# Moteino_Leo-OLM.net
KiCad netlist of a schematic drawn in EAGLE
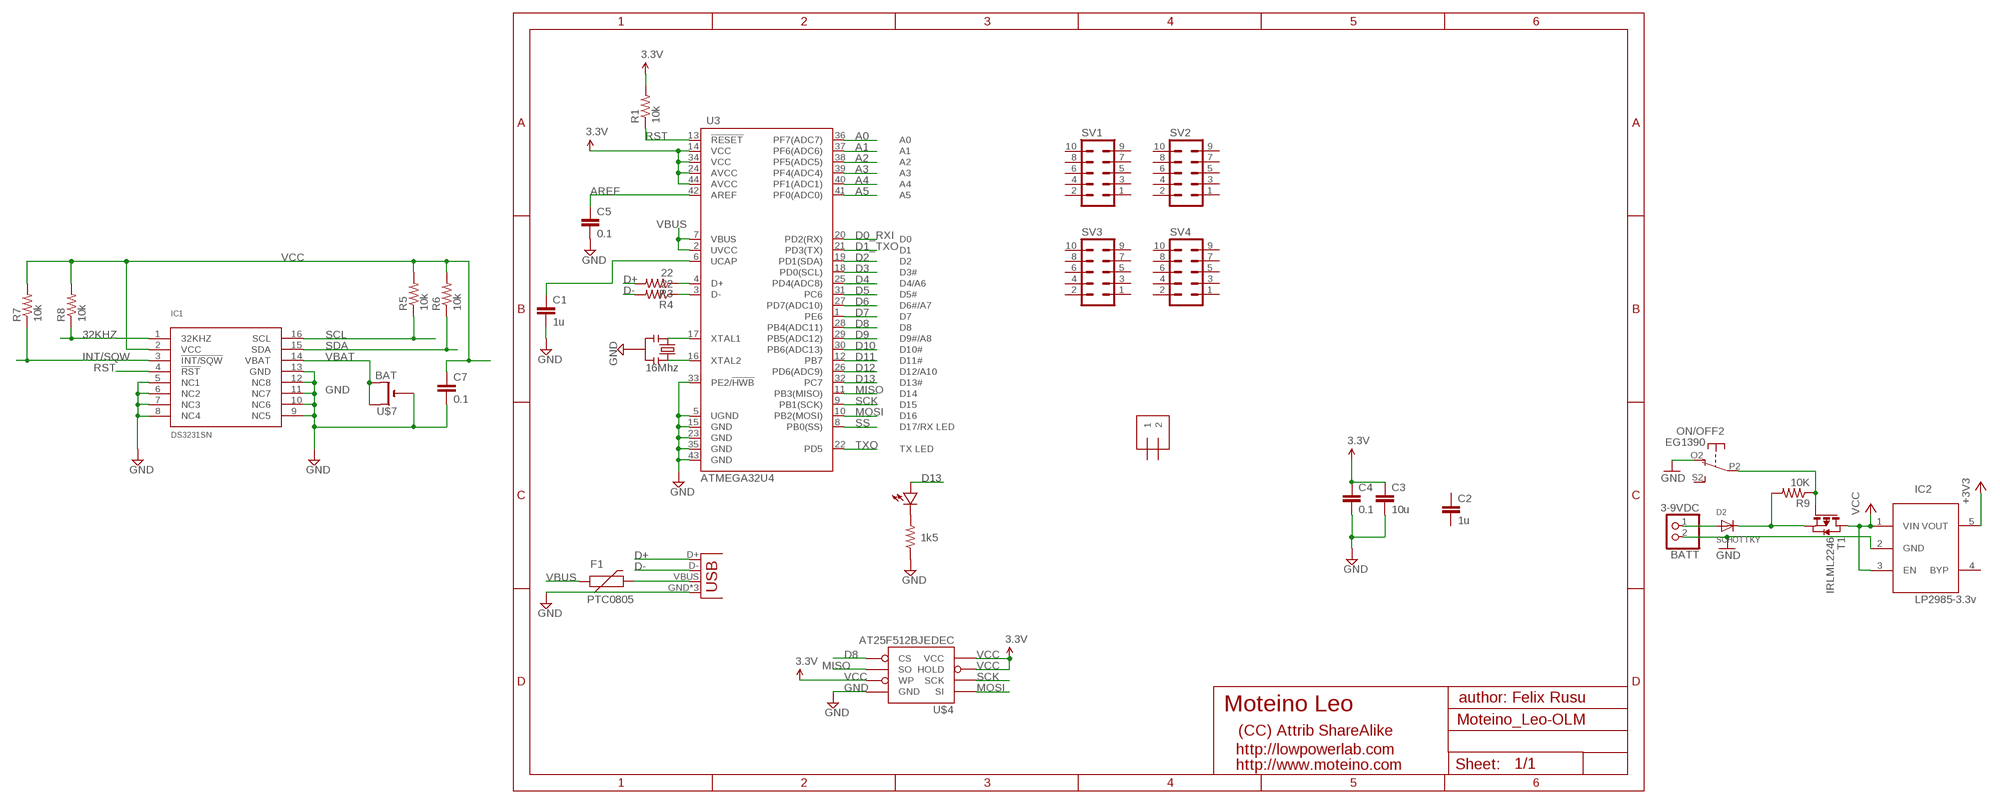
[diagram p0: schematic, sheet 1]

(export (version "E")
  (design (tool "Eeschema 10.0.6"))
  (components
    (comp (ref "BATT")
      (value "3-9VDC")
      (footprint "eagle-import:JST-PH-2-SMT-RA")
      (libsource (lib "eagle-import") (part "JST_2PIN-SMT-RA"))
    )
    (comp (ref "C1")
      (value "1u")
      (footprint "eagle-import:0603-CAP")
      (libsource (lib "eagle-import") (part "CAP0603-CAP"))
    )
    (comp (ref "C2")
      (value "1u")
      (footprint "eagle-import:0603-CAP")
      (libsource (lib "eagle-import") (part "CAP0603-CAP"))
    )
    (comp (ref "C3")
      (value "10u")
      (footprint "eagle-import:0805-CAP")
      (libsource (lib "eagle-import") (part "CAP0805-CAP"))
    )
    (comp (ref "C4")
      (value "0.1")
      (footprint "eagle-import:0603-CAP")
      (libsource (lib "eagle-import") (part "CAP0603-CAP"))
    )
    (comp (ref "C5")
      (value "0.1")
      (footprint "eagle-import:0603-CAP")
      (libsource (lib "eagle-import") (part "CAP0603-CAP"))
    )
    (comp (ref "C7")
      (value "0.1")
      (footprint "eagle-import:0603-CAP")
      (libsource (lib "eagle-import") (part "CAP0603-CAP"))
    )
    (comp (ref "D2")
      (value "SCHOTTKY")
      (footprint "eagle-import:SOD-123")
      (libsource (lib "eagle-import") (part "DIODESOD-123"))
    )
    (comp (ref "F1")
      (value "PTC0805")
      (footprint "eagle-import:0805-PTC")
      (libsource (lib "eagle-import") (part "PTC0805"))
    )
    (comp (ref "IC1")
      (value "DS3231SN")
      (footprint "eagle-import:SO16W")
      (libsource (lib "eagle-import") (part "DS3231SN"))
    )
    (comp (ref "IC2")
      (value "LP2985-3.3v")
      (footprint "eagle-import:SOT23-5L")
      (libsource (lib "eagle-import") (part "LP298XS"))
    )
    (comp (ref "J1")
      (value "1X2-3.5MM")
      (footprint "eagle-import:1X2-3.5MM")
      (libsource (lib "eagle-import") (part "1X2-3.5MM"))
    )
    (comp (ref "JP3")
      (value "USB-MICROB")
      (footprint "eagle-import:USB-MICROB")
      (libsource (lib "eagle-import") (part "USB-MICROB"))
    )
    (comp (ref "ON/OFF")
      (value "EG1390")
      (footprint "eagle-import:EG1390")
      (libsource (lib "eagle-import") (part "DPDT-EG1390"))
    )
    (comp (ref "R1")
      (value "10k")
      (footprint "eagle-import:0603-RES")
      (libsource (lib "eagle-import") (part "RESISTOR0603-RES"))
    )
    (comp (ref "R2")
      (value "1k5")
      (footprint "eagle-import:0603-RES")
      (libsource (lib "eagle-import") (part "RESISTOR0603-RES"))
    )
    (comp (ref "R3")
      (value "22")
      (footprint "eagle-import:0603-RES")
      (libsource (lib "eagle-import") (part "RESISTOR0603-RES"))
    )
    (comp (ref "R4")
      (value "22")
      (footprint "eagle-import:0603-RES")
      (libsource (lib "eagle-import") (part "RESISTOR0603-RES"))
    )
    (comp (ref "R5")
      (value "10k")
      (footprint "eagle-import:0603-RES")
      (libsource (lib "eagle-import") (part "RESISTOR0603-RES"))
    )
    (comp (ref "R6")
      (value "10k")
      (footprint "eagle-import:0603-RES")
      (libsource (lib "eagle-import") (part "RESISTOR0603-RES"))
    )
    (comp (ref "R7")
      (value "10k")
      (footprint "eagle-import:0603-RES")
      (libsource (lib "eagle-import") (part "RESISTOR0603-RES"))
    )
    (comp (ref "R8")
      (value "10k")
      (footprint "eagle-import:0603-RES")
      (libsource (lib "eagle-import") (part "RESISTOR0603-RES"))
    )
    (comp (ref "R9")
      (value "10K")
      (footprint "eagle-import:R0805")
      (libsource (lib "eagle-import") (part "R-US_R0805"))
    )
    (comp (ref "SV1")
      (value "MA05-2")
      (footprint "eagle-import:MA05-2")
      (libsource (lib "eagle-import") (part "MA05-2"))
    )
    (comp (ref "SV2")
      (value "MA05-2")
      (footprint "eagle-import:MA05-2")
      (libsource (lib "eagle-import") (part "MA05-2"))
    )
    (comp (ref "SV3")
      (value "MA05-2")
      (footprint "eagle-import:MA05-2")
      (libsource (lib "eagle-import") (part "MA05-2"))
    )
    (comp (ref "SV4")
      (value "MA05-2")
      (footprint "eagle-import:MA05-2")
      (libsource (lib "eagle-import") (part "MA05-2"))
    )
    (comp (ref "T1")
      (value "IRLML2246")
      (footprint "eagle-import:SOT-23")
      (libsource (lib "eagle-import") (part "PMOSSOT23"))
    )
    (comp (ref "U$2")
      (value "LED0603")
      (footprint "eagle-import:0603-LED")
      (libsource (lib "eagle-import") (part "LED0603"))
    )
    (comp (ref "U$4")
      (value "AT25F512BJEDEC")
      (footprint "eagle-import:SO08")
      (libsource (lib "eagle-import") (part "AT25F512BJEDEC"))
    )
    (comp (ref "U$7")
      (value "BAT")
      (footprint "eagle-import:CR1220-SMD")
      (libsource (lib "eagle-import") (part "CR1220SMT"))
    )
    (comp (ref "U3")
      (value "ATMEGA32U4")
      (footprint "eagle-import:QFN-44-NOPAD")
      (libsource (lib "eagle-import") (part "ATMEGA32U4QFN2"))
    )
    (comp (ref "X1")
      (value "16Mhz")
      (footprint "eagle-import:RESONATOR-SMD")
      (libsource (lib "eagle-import") (part "RESONATORSMD"))
    )
  )
  (nets
    (net (code "1") (name "+3V3") (class "Default")
      (node (ref "IC2") (pin "5") (pinfunction "VOUT_5") (pintype "bidirectional"))
    )
    (net (code "2") (name "/32KHZ") (class "Default")
      (node (ref "IC1") (pin "1") (pinfunction "32KHZ_1") (pintype "bidirectional"))
      (node (ref "R8") (pin "1") (pinfunction "1_1") (pintype "passive"))
    )
    (net (code "3") (name "/A0") (class "Default")
      (node (ref "U3") (pin "36") (pinfunction "PF7(ADC7)_36") (pintype "bidirectional"))
    )
    (net (code "4") (name "/A1") (class "Default")
      (node (ref "U3") (pin "37") (pinfunction "PF6(ADC6)_37") (pintype "bidirectional"))
    )
    (net (code "5") (name "/A2") (class "Default")
      (node (ref "U3") (pin "38") (pinfunction "PF5(ADC5)_38") (pintype "bidirectional"))
    )
    (net (code "6") (name "/A3") (class "Default")
      (node (ref "U3") (pin "39") (pinfunction "PF4(ADC4)_39") (pintype "bidirectional"))
    )
    (net (code "7") (name "/A4") (class "Default")
      (node (ref "U3") (pin "40") (pinfunction "PF1(ADC1)_40") (pintype "bidirectional"))
    )
    (net (code "8") (name "/A5") (class "Default")
      (node (ref "U3") (pin "41") (pinfunction "PF0(ADC0)_41") (pintype "bidirectional"))
    )
    (net (code "9") (name "/AREF") (class "Default")
      (node (ref "C5") (pin "1") (pinfunction "1_1") (pintype "passive"))
      (node (ref "U3") (pin "42") (pinfunction "AREF_42") (pintype "bidirectional"))
    )
    (net (code "10") (name "/D+") (class "Default")
      (node (ref "JP3") (pin "D+") (pinfunction "D+_D+") (pintype "bidirectional"))
      (node (ref "R3") (pin "2") (pinfunction "2_2") (pintype "passive"))
    )
    (net (code "11") (name "/D-") (class "Default")
      (node (ref "JP3") (pin "D-") (pinfunction "D-_D-") (pintype "bidirectional"))
      (node (ref "R4") (pin "2") (pinfunction "2_2") (pintype "passive"))
    )
    (net (code "12") (name "/D0_RXI") (class "Default")
      (node (ref "U3") (pin "20") (pinfunction "PD2(RX)_20") (pintype "bidirectional"))
    )
    (net (code "13") (name "/D1_TXO") (class "Default")
      (node (ref "U3") (pin "21") (pinfunction "PD3(TX)_21") (pintype "bidirectional"))
    )
    (net (code "14") (name "/D2") (class "Default")
      (node (ref "U3") (pin "19") (pinfunction "PD1(SDA)_19") (pintype "bidirectional"))
    )
    (net (code "15") (name "/D3") (class "Default")
      (node (ref "U3") (pin "18") (pinfunction "PD0(SCL)_18") (pintype "bidirectional"))
    )
    (net (code "16") (name "/D4") (class "Default")
      (node (ref "U3") (pin "25") (pinfunction "PD4(ADC8)_25") (pintype "bidirectional"))
    )
    (net (code "17") (name "/D5") (class "Default")
      (node (ref "U3") (pin "31") (pinfunction "PC6_31") (pintype "bidirectional"))
    )
    (net (code "18") (name "/D6") (class "Default")
      (node (ref "U3") (pin "27") (pinfunction "PD7(ADC10)_27") (pintype "bidirectional"))
    )
    (net (code "19") (name "/D7") (class "Default")
      (node (ref "U3") (pin "1") (pinfunction "PE6_1") (pintype "bidirectional"))
    )
    (net (code "20") (name "/D8") (class "Default")
      (node (ref "U$4") (pin "1_CS") (pinfunction "CS_1_CS") (pintype "bidirectional"))
      (node (ref "U3") (pin "28") (pinfunction "PB4(ADC11)_28") (pintype "bidirectional"))
    )
    (net (code "21") (name "/D9") (class "Default")
      (node (ref "U3") (pin "29") (pinfunction "PB5(ADC12)_29") (pintype "bidirectional"))
    )
    (net (code "22") (name "/D10") (class "Default")
      (node (ref "U3") (pin "30") (pinfunction "PB6(ADC13)_30") (pintype "bidirectional"))
    )
    (net (code "23") (name "/D11") (class "Default")
      (node (ref "U3") (pin "12") (pinfunction "PB7_12") (pintype "bidirectional"))
    )
    (net (code "24") (name "/D12") (class "Default")
      (node (ref "U3") (pin "26") (pinfunction "PD6(ADC9)_26") (pintype "bidirectional"))
    )
    (net (code "25") (name "/D13") (class "Default")
      (node (ref "U$2") (pin "PLUS") (pinfunction "PLUS_PLUS") (pintype "passive"))
      (node (ref "U3") (pin "32") (pinfunction "PC7_32") (pintype "bidirectional"))
    )
    (net (code "26") (name "/INT{slash}SQW") (class "Default")
      (node (ref "IC1") (pin "3") (pinfunction "~{INT/SQW}_3") (pintype "bidirectional"))
      (node (ref "R7") (pin "1") (pinfunction "1_1") (pintype "passive"))
    )
    (net (code "27") (name "/MISO") (class "Default")
      (node (ref "U$4") (pin "2_SO") (pinfunction "SO_2_SO") (pintype "bidirectional"))
      (node (ref "U3") (pin "11") (pinfunction "PB3(MISO)_11") (pintype "bidirectional"))
    )
    (net (code "28") (name "/MOSI") (class "Default")
      (node (ref "U$4") (pin "5_SI") (pinfunction "SI_5_SI") (pintype "bidirectional"))
      (node (ref "U3") (pin "10") (pinfunction "PB2(MOSI)_10") (pintype "bidirectional"))
    )
    (net (code "29") (name "/RST") (class "Default")
      (node (ref "IC1") (pin "4") (pinfunction "~{RST}_4") (pintype "bidirectional"))
      (node (ref "R1") (pin "1") (pinfunction "1_1") (pintype "passive"))
      (node (ref "U3") (pin "13") (pinfunction "~{RESET}_13") (pintype "bidirectional"))
    )
    (net (code "30") (name "/SCK") (class "Default")
      (node (ref "U$4") (pin "6_SCK") (pinfunction "SCK_6_SCK") (pintype "bidirectional"))
      (node (ref "U3") (pin "9") (pinfunction "PB1(SCK)_9") (pintype "bidirectional"))
    )
    (net (code "31") (name "/SCL") (class "Default")
      (node (ref "IC1") (pin "16") (pinfunction "SCL_16") (pintype "bidirectional"))
      (node (ref "R5") (pin "1") (pinfunction "1_1") (pintype "passive"))
    )
    (net (code "32") (name "/SDA") (class "Default")
      (node (ref "IC1") (pin "15") (pinfunction "SDA_15") (pintype "bidirectional"))
      (node (ref "R6") (pin "1") (pinfunction "1_1") (pintype "passive"))
    )
    (net (code "33") (name "/SS") (class "Default")
      (node (ref "U3") (pin "8") (pinfunction "PB0(SS)_8") (pintype "bidirectional"))
    )
    (net (code "34") (name "/TXO") (class "Default")
      (node (ref "U3") (pin "22") (pinfunction "PD5_22") (pintype "bidirectional"))
    )
    (net (code "35") (name "/VBAT") (class "Default")
      (node (ref "IC1") (pin "14") (pinfunction "VBAT_14") (pintype "bidirectional"))
      (node (ref "U$7") (pin "+$1") (pinfunction "+_+$1") (pintype "passive"))
      (node (ref "U$7") (pin "+$2") (pinfunction "+1_+$2") (pintype "passive"))
    )
    (net (code "36") (name "/VBUS") (class "Default")
      (node (ref "F1") (pin "1") (pinfunction "1_1") (pintype "bidirectional"))
      (node (ref "U3") (pin "2") (pinfunction "UVCC_2") (pintype "bidirectional"))
      (node (ref "U3") (pin "7") (pinfunction "VBUS_7") (pintype "bidirectional"))
    )
    (net (code "37") (name "3.3V") (class "Default")
      (node (ref "C3") (pin "1") (pinfunction "1_1") (pintype "passive"))
      (node (ref "C4") (pin "1") (pinfunction "1_1") (pintype "passive"))
      (node (ref "C7") (pin "1") (pinfunction "1_1") (pintype "passive"))
      (node (ref "IC1") (pin "2") (pinfunction "VCC_2") (pintype "bidirectional"))
      (node (ref "IC2") (pin "1") (pinfunction "VIN_1") (pintype "bidirectional"))
      (node (ref "IC2") (pin "3") (pinfunction "EN_3") (pintype "bidirectional"))
      (node (ref "R1") (pin "2") (pinfunction "2_2") (pintype "passive"))
      (node (ref "R5") (pin "2") (pinfunction "2_2") (pintype "passive"))
      (node (ref "R6") (pin "2") (pinfunction "2_2") (pintype "passive"))
      (node (ref "R7") (pin "2") (pinfunction "2_2") (pintype "passive"))
      (node (ref "R8") (pin "2") (pinfunction "2_2") (pintype "passive"))
      (node (ref "T1") (pin "1") (pinfunction "D_1") (pintype "passive"))
      (node (ref "U$4") (pin "3_WP") (pinfunction "WP_3_WP") (pintype "bidirectional"))
      (node (ref "U$4") (pin "7_HOLD") (pinfunction "HOLD_7_HOLD") (pintype "bidirectional"))
      (node (ref "U$4") (pin "8_VCC") (pinfunction "VCC_8_VCC") (pintype "bidirectional"))
      (node (ref "U3") (pin "14") (pinfunction "VCC_14") (pintype "bidirectional"))
      (node (ref "U3") (pin "24") (pinfunction "AVCC_24") (pintype "bidirectional"))
      (node (ref "U3") (pin "34") (pinfunction "VCC_34") (pintype "bidirectional"))
      (node (ref "U3") (pin "44") (pinfunction "AVCC_44") (pintype "bidirectional"))
    )
    (net (code "38") (name "GND") (class "Default")
      (node (ref "BATT") (pin "2") (pinfunction "1_2") (pintype "passive"))
      (node (ref "C1") (pin "2") (pinfunction "2_2") (pintype "passive"))
      (node (ref "C3") (pin "2") (pinfunction "2_2") (pintype "passive"))
      (node (ref "C4") (pin "2") (pinfunction "2_2") (pintype "passive"))
      (node (ref "C5") (pin "2") (pinfunction "2_2") (pintype "passive"))
      (node (ref "C7") (pin "2") (pinfunction "2_2") (pintype "passive"))
      (node (ref "IC1") (pin "10") (pinfunction "NC6_10") (pintype "bidirectional"))
      (node (ref "IC1") (pin "11") (pinfunction "NC7_11") (pintype "bidirectional"))
      (node (ref "IC1") (pin "12") (pinfunction "NC8_12") (pintype "bidirectional"))
      (node (ref "IC1") (pin "13") (pinfunction "GND_13") (pintype "bidirectional"))
      (node (ref "IC1") (pin "5") (pinfunction "NC1_5") (pintype "bidirectional"))
      (node (ref "IC1") (pin "6") (pinfunction "NC2_6") (pintype "bidirectional"))
      (node (ref "IC1") (pin "7") (pinfunction "NC3_7") (pintype "bidirectional"))
      (node (ref "IC1") (pin "8") (pinfunction "NC4_8") (pintype "bidirectional"))
      (node (ref "IC1") (pin "9") (pinfunction "NC5_9") (pintype "bidirectional"))
      (node (ref "IC2") (pin "2") (pinfunction "GND_2") (pintype "bidirectional"))
      (node (ref "JP3") (pin "GND") (pinfunction "GND_GND") (pintype "bidirectional"))
      (node (ref "JP3") (pin "MT1") (pinfunction "GND_MT1") (pintype "bidirectional"))
      (node (ref "JP3") (pin "MT2") (pinfunction "GND_MT2") (pintype "bidirectional"))
      (node (ref "ON/OFF") (pin "O2") (pinfunction "O_O2") (pintype "passive"))
      (node (ref "R2") (pin "1") (pinfunction "1_1") (pintype "passive"))
      (node (ref "U$4") (pin "4_GND") (pinfunction "GND_4_GND") (pintype "bidirectional"))
      (node (ref "U$7") (pin "-") (pinfunction "-_-") (pintype "passive"))
      (node (ref "U3") (pin "15") (pinfunction "GND_15") (pintype "bidirectional"))
      (node (ref "U3") (pin "23") (pinfunction "GND_23") (pintype "bidirectional"))
      (node (ref "U3") (pin "33") (pinfunction "PE2/~{HWB}_33") (pintype "bidirectional"))
      (node (ref "U3") (pin "35") (pinfunction "GND_35") (pintype "bidirectional"))
      (node (ref "U3") (pin "43") (pinfunction "GND_43") (pintype "bidirectional"))
      (node (ref "U3") (pin "5") (pinfunction "UGND_5") (pintype "bidirectional"))
      (node (ref "X1") (pin "2") (pinfunction "2_2") (pintype "passive"))
    )
    (net (code "39") (name "Net-(BATT-2)") (class "Default")
      (node (ref "BATT") (pin "1") (pinfunction "2_1") (pintype "passive"))
      (node (ref "D2") (pin "A") (pinfunction "A_A") (pintype "passive"))
    )
    (net (code "40") (name "Net-(F1-Pad2)") (class "Default")
      (node (ref "F1") (pin "2") (pinfunction "2_2") (pintype "bidirectional"))
      (node (ref "JP3") (pin "VBUS") (pinfunction "VBUS_VBUS") (pintype "bidirectional"))
    )
    (net (code "41") (name "Net-(ON/OFFB-P)") (class "Default")
      (node (ref "ON/OFF") (pin "P2") (pinfunction "P_P2") (pintype "passive"))
      (node (ref "R9") (pin "1") (pinfunction "1_1") (pintype "passive"))
      (node (ref "T1") (pin "3") (pinfunction "G_3") (pintype "passive"))
    )
    (net (code "42") (name "Net-(R2-Pad2)") (class "Default")
      (node (ref "R2") (pin "2") (pinfunction "2_2") (pintype "passive"))
      (node (ref "U$2") (pin "MINUS") (pinfunction "MINUS_MINUS") (pintype "passive"))
    )
    (net (code "43") (name "Net-(T1-S)") (class "Default")
      (node (ref "D2") (pin "C") (pinfunction "C_C") (pintype "passive"))
      (node (ref "R9") (pin "2") (pinfunction "2_2") (pintype "passive"))
      (node (ref "T1") (pin "2") (pinfunction "S_2") (pintype "passive"))
    )
    (net (code "44") (name "Net-(U3-D+)") (class "Default")
      (node (ref "R3") (pin "1") (pinfunction "1_1") (pintype "passive"))
      (node (ref "U3") (pin "4") (pinfunction "D+_4") (pintype "bidirectional"))
    )
    (net (code "45") (name "Net-(U3-D-)") (class "Default")
      (node (ref "R4") (pin "1") (pinfunction "1_1") (pintype "passive"))
      (node (ref "U3") (pin "3") (pinfunction "D-_3") (pintype "bidirectional"))
    )
    (net (code "46") (name "Net-(U3-UCAP)") (class "Default")
      (node (ref "C1") (pin "1") (pinfunction "1_1") (pintype "passive"))
      (node (ref "U3") (pin "6") (pinfunction "UCAP_6") (pintype "bidirectional"))
    )
    (net (code "47") (name "Net-(U3-XTAL1)") (class "Default")
      (node (ref "U3") (pin "17") (pinfunction "XTAL1_17") (pintype "bidirectional"))
      (node (ref "X1") (pin "1") (pinfunction "1_1") (pintype "passive"))
    )
    (net (code "48") (name "Net-(U3-XTAL2)") (class "Default")
      (node (ref "U3") (pin "16") (pinfunction "XTAL2_16") (pintype "bidirectional"))
      (node (ref "X1") (pin "3") (pinfunction "3_3") (pintype "passive"))
    )
    (net (code "49") (name "unconnected-(C2-Pad1)") (class "Default")
      (node (ref "C2") (pin "1") (pinfunction "1_1") (pintype "passive"))
    )
    (net (code "50") (name "unconnected-(C2-Pad2)") (class "Default")
      (node (ref "C2") (pin "2") (pinfunction "2_2") (pintype "passive"))
    )
    (net (code "51") (name "unconnected-(IC2-BYP-Pad4)") (class "Default")
      (node (ref "IC2") (pin "4") (pinfunction "BYP_4") (pintype "bidirectional"))
    )
    (net (code "52") (name "unconnected-(J1-Pad1)") (class "Default")
      (node (ref "J1") (pin "1") (pinfunction "1_1") (pintype "passive"))
    )
    (net (code "53") (name "unconnected-(J1-Pad2)") (class "Default")
      (node (ref "J1") (pin "2") (pinfunction "2_2") (pintype "passive"))
    )
    (net (code "54") (name "unconnected-(ON/OFFB-S-PadS2)") (class "Default")
      (node (ref "ON/OFF") (pin "S2") (pinfunction "S_S2") (pintype "passive"))
    )
    (net (code "55") (name "unconnected-(SV1-Pad1)") (class "Default")
      (node (ref "SV1") (pin "1") (pinfunction "1_1") (pintype "passive"))
    )
    (net (code "56") (name "unconnected-(SV1-Pad2)") (class "Default")
      (node (ref "SV1") (pin "2") (pinfunction "2_2") (pintype "passive"))
    )
    (net (code "57") (name "unconnected-(SV1-Pad3)") (class "Default")
      (node (ref "SV1") (pin "3") (pinfunction "3_3") (pintype "passive"))
    )
    (net (code "58") (name "unconnected-(SV1-Pad4)") (class "Default")
      (node (ref "SV1") (pin "4") (pinfunction "4_4") (pintype "passive"))
    )
    (net (code "59") (name "unconnected-(SV1-Pad5)") (class "Default")
      (node (ref "SV1") (pin "5") (pinfunction "5_5") (pintype "passive"))
    )
    (net (code "60") (name "unconnected-(SV1-Pad6)") (class "Default")
      (node (ref "SV1") (pin "6") (pinfunction "6_6") (pintype "passive"))
    )
    (net (code "61") (name "unconnected-(SV1-Pad7)") (class "Default")
      (node (ref "SV1") (pin "7") (pinfunction "7_7") (pintype "passive"))
    )
    (net (code "62") (name "unconnected-(SV1-Pad8)") (class "Default")
      (node (ref "SV1") (pin "8") (pinfunction "8_8") (pintype "passive"))
    )
    (net (code "63") (name "unconnected-(SV1-Pad9)") (class "Default")
      (node (ref "SV1") (pin "9") (pinfunction "9_9") (pintype "passive"))
    )
    (net (code "64") (name "unconnected-(SV1-Pad10)") (class "Default")
      (node (ref "SV1") (pin "10") (pinfunction "10_10") (pintype "passive"))
    )
    (net (code "65") (name "unconnected-(SV2-Pad1)") (class "Default")
      (node (ref "SV2") (pin "1") (pinfunction "1_1") (pintype "passive"))
    )
    (net (code "66") (name "unconnected-(SV2-Pad2)") (class "Default")
      (node (ref "SV2") (pin "2") (pinfunction "2_2") (pintype "passive"))
    )
    (net (code "67") (name "unconnected-(SV2-Pad3)") (class "Default")
      (node (ref "SV2") (pin "3") (pinfunction "3_3") (pintype "passive"))
    )
    (net (code "68") (name "unconnected-(SV2-Pad4)") (class "Default")
      (node (ref "SV2") (pin "4") (pinfunction "4_4") (pintype "passive"))
    )
    (net (code "69") (name "unconnected-(SV2-Pad5)") (class "Default")
      (node (ref "SV2") (pin "5") (pinfunction "5_5") (pintype "passive"))
    )
    (net (code "70") (name "unconnected-(SV2-Pad6)") (class "Default")
      (node (ref "SV2") (pin "6") (pinfunction "6_6") (pintype "passive"))
    )
    (net (code "71") (name "unconnected-(SV2-Pad7)") (class "Default")
      (node (ref "SV2") (pin "7") (pinfunction "7_7") (pintype "passive"))
    )
    (net (code "72") (name "unconnected-(SV2-Pad8)") (class "Default")
      (node (ref "SV2") (pin "8") (pinfunction "8_8") (pintype "passive"))
    )
    (net (code "73") (name "unconnected-(SV2-Pad9)") (class "Default")
      (node (ref "SV2") (pin "9") (pinfunction "9_9") (pintype "passive"))
    )
    (net (code "74") (name "unconnected-(SV2-Pad10)") (class "Default")
      (node (ref "SV2") (pin "10") (pinfunction "10_10") (pintype "passive"))
    )
    (net (code "75") (name "unconnected-(SV3-Pad1)") (class "Default")
      (node (ref "SV3") (pin "1") (pinfunction "1_1") (pintype "passive"))
    )
    (net (code "76") (name "unconnected-(SV3-Pad2)") (class "Default")
      (node (ref "SV3") (pin "2") (pinfunction "2_2") (pintype "passive"))
    )
    (net (code "77") (name "unconnected-(SV3-Pad3)") (class "Default")
      (node (ref "SV3") (pin "3") (pinfunction "3_3") (pintype "passive"))
    )
    (net (code "78") (name "unconnected-(SV3-Pad4)") (class "Default")
      (node (ref "SV3") (pin "4") (pinfunction "4_4") (pintype "passive"))
    )
    (net (code "79") (name "unconnected-(SV3-Pad5)") (class "Default")
      (node (ref "SV3") (pin "5") (pinfunction "5_5") (pintype "passive"))
    )
    (net (code "80") (name "unconnected-(SV3-Pad6)") (class "Default")
      (node (ref "SV3") (pin "6") (pinfunction "6_6") (pintype "passive"))
    )
    (net (code "81") (name "unconnected-(SV3-Pad7)") (class "Default")
      (node (ref "SV3") (pin "7") (pinfunction "7_7") (pintype "passive"))
    )
    (net (code "82") (name "unconnected-(SV3-Pad8)") (class "Default")
      (node (ref "SV3") (pin "8") (pinfunction "8_8") (pintype "passive"))
    )
    (net (code "83") (name "unconnected-(SV3-Pad9)") (class "Default")
      (node (ref "SV3") (pin "9") (pinfunction "9_9") (pintype "passive"))
    )
    (net (code "84") (name "unconnected-(SV3-Pad10)") (class "Default")
      (node (ref "SV3") (pin "10") (pinfunction "10_10") (pintype "passive"))
    )
    (net (code "85") (name "unconnected-(SV4-Pad1)") (class "Default")
      (node (ref "SV4") (pin "1") (pinfunction "1_1") (pintype "passive"))
    )
    (net (code "86") (name "unconnected-(SV4-Pad2)") (class "Default")
      (node (ref "SV4") (pin "2") (pinfunction "2_2") (pintype "passive"))
    )
    (net (code "87") (name "unconnected-(SV4-Pad3)") (class "Default")
      (node (ref "SV4") (pin "3") (pinfunction "3_3") (pintype "passive"))
    )
    (net (code "88") (name "unconnected-(SV4-Pad4)") (class "Default")
      (node (ref "SV4") (pin "4") (pinfunction "4_4") (pintype "passive"))
    )
    (net (code "89") (name "unconnected-(SV4-Pad5)") (class "Default")
      (node (ref "SV4") (pin "5") (pinfunction "5_5") (pintype "passive"))
    )
    (net (code "90") (name "unconnected-(SV4-Pad6)") (class "Default")
      (node (ref "SV4") (pin "6") (pinfunction "6_6") (pintype "passive"))
    )
    (net (code "91") (name "unconnected-(SV4-Pad7)") (class "Default")
      (node (ref "SV4") (pin "7") (pinfunction "7_7") (pintype "passive"))
    )
    (net (code "92") (name "unconnected-(SV4-Pad8)") (class "Default")
      (node (ref "SV4") (pin "8") (pinfunction "8_8") (pintype "passive"))
    )
    (net (code "93") (name "unconnected-(SV4-Pad9)") (class "Default")
      (node (ref "SV4") (pin "9") (pinfunction "9_9") (pintype "passive"))
    )
    (net (code "94") (name "unconnected-(SV4-Pad10)") (class "Default")
      (node (ref "SV4") (pin "10") (pinfunction "10_10") (pintype "passive"))
    )
  )
)
